# motor_driver.net
KiCad netlist of a schematic drawn in EAGLE
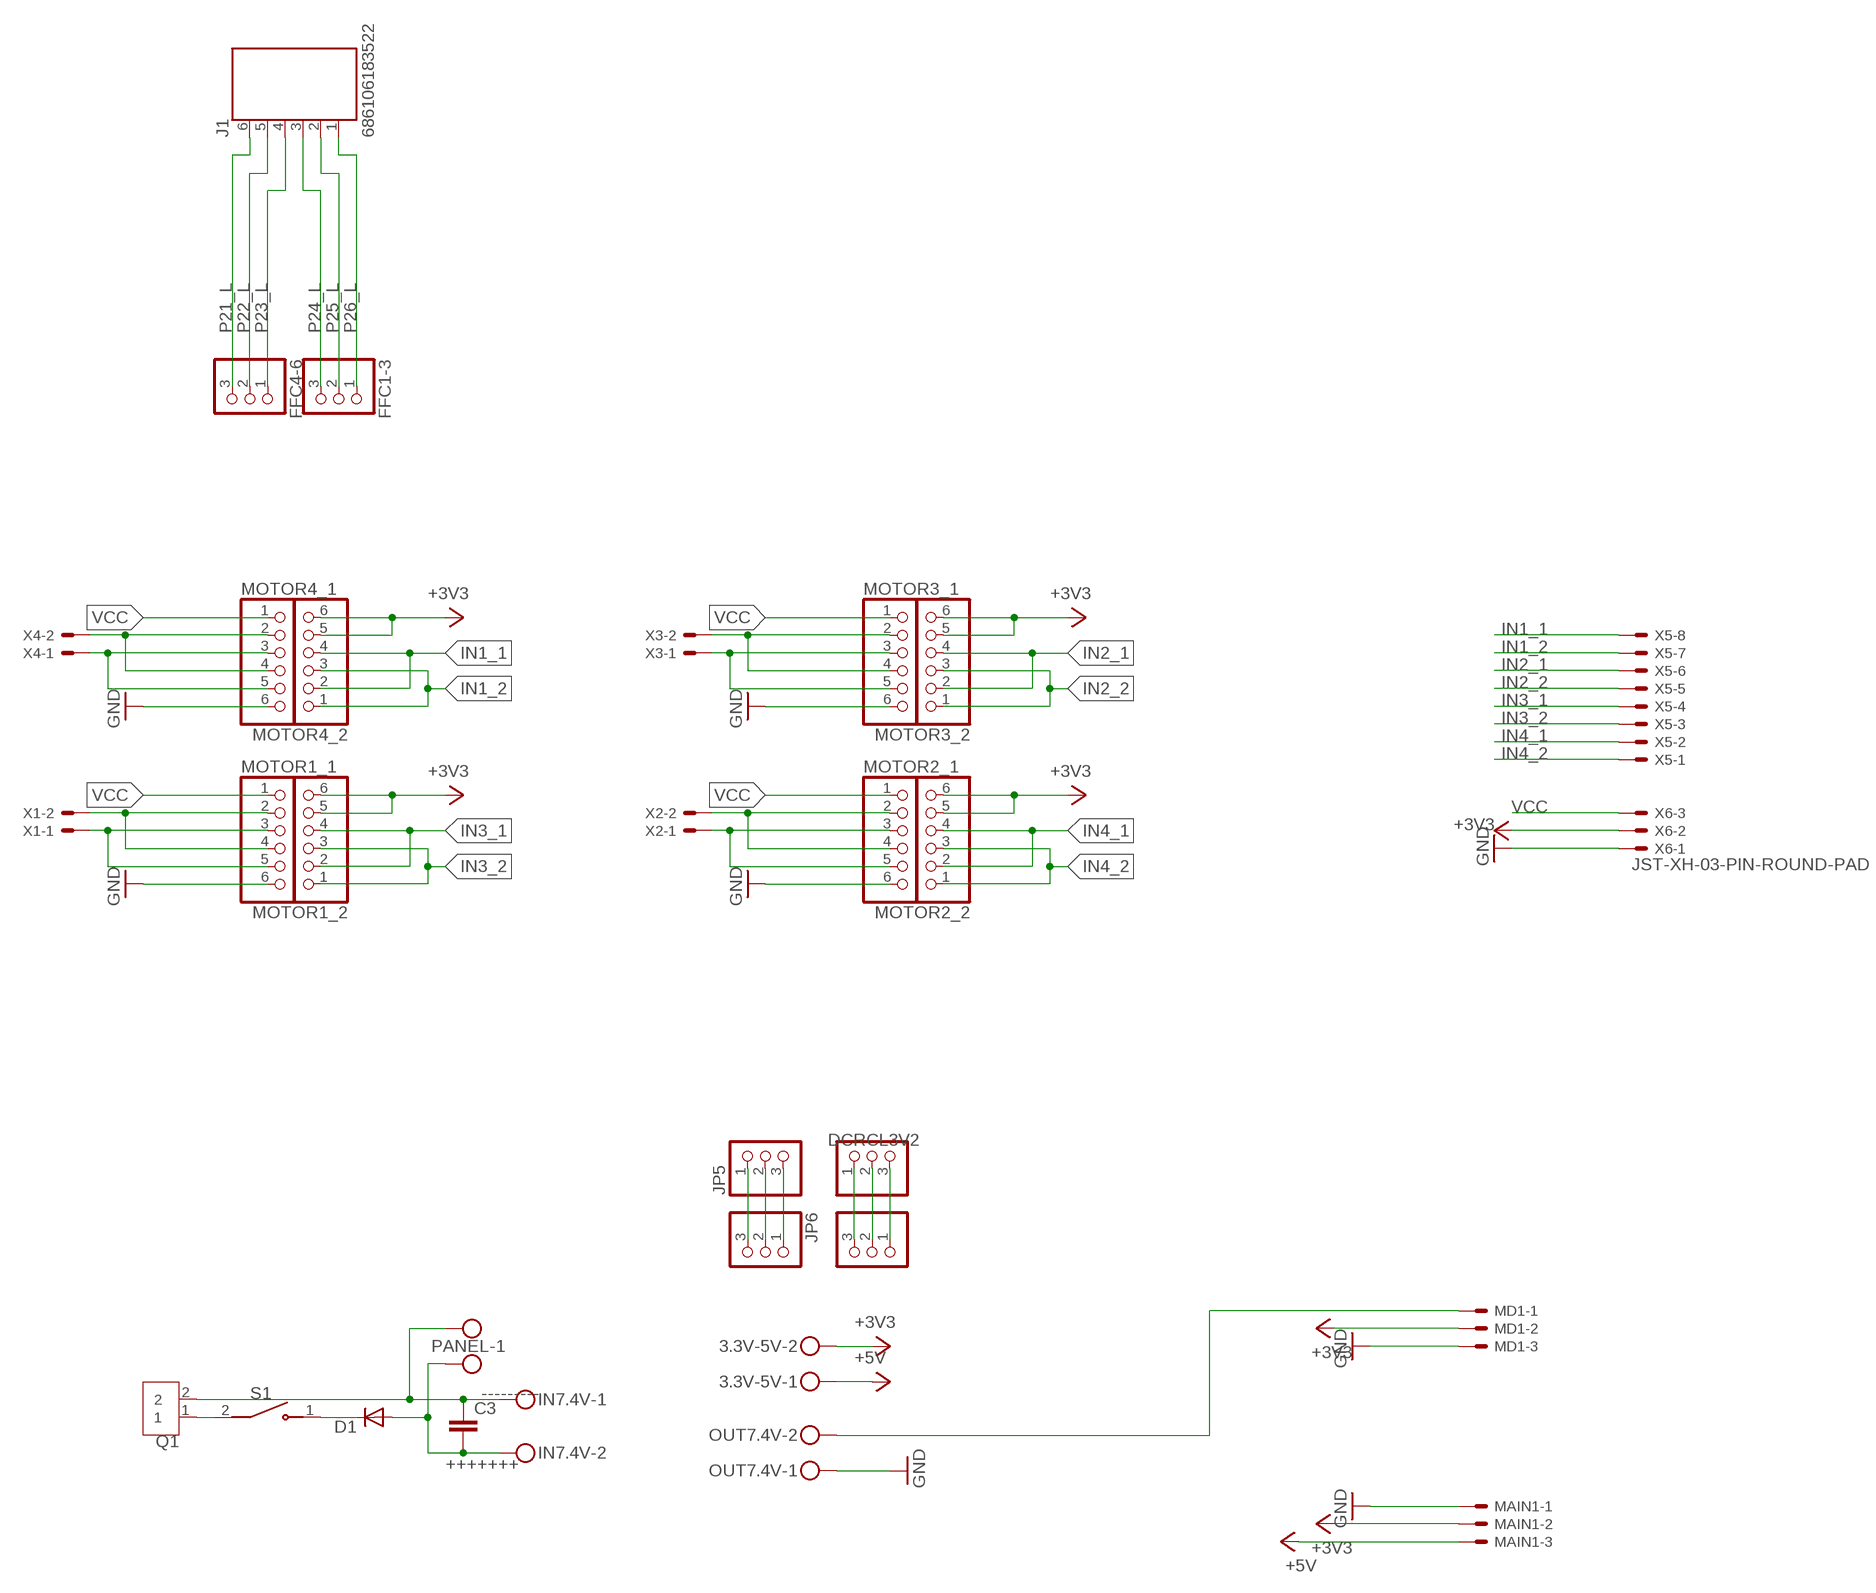
[diagram p0: schematic, sheet 1]

(export (version "E")
  (design (tool "Eeschema 10.0.6"))
  (components
    (comp (ref "3.3V-5V")
      (value "MKDSN1,5/2-5,08")
      (footprint "eagle-import:MKDSN1,5_2-5,08")
      (libsource (lib "eagle-import") (part "MKDSN1,5/2-5,08"))
    )
    (comp (ref "C3")
      (value "C-EU025-030X050")
      (footprint "eagle-import:C025-030X050")
      (libsource (lib "eagle-import") (part "C-EU025-030X050"))
    )
    (comp (ref "D1")
      (value "DIODE-SMC")
      (footprint "eagle-import:SMC")
      (libsource (lib "eagle-import") (part "DIODE-SMC"))
    )
    (comp (ref "DCRC3V1")
      (value "PINHD-1X3")
      (footprint "eagle-import:1X03")
      (libsource (lib "eagle-import") (part "PINHD-1X3"))
    )
    (comp (ref "DCRCL3V2")
      (value "PINHD-1X3")
      (footprint "eagle-import:1X03")
      (libsource (lib "eagle-import") (part "PINHD-1X3"))
    )
    (comp (ref "FFC1-3")
      (value "PINHD-1X03_2.54-S")
      (footprint "eagle-import:1X03-S")
      (libsource (lib "eagle-import") (part "PINHD-1X03_2.54-S"))
    )
    (comp (ref "FFC4-6")
      (value "PINHD-1X03_2.54-S")
      (footprint "eagle-import:1X03-S")
      (libsource (lib "eagle-import") (part "PINHD-1X03_2.54-S"))
    )
    (comp (ref "IN7.4V")
      (value "MKDSN1,5/2-5,08")
      (footprint "eagle-import:MKDSN1,5_2-5,08")
      (libsource (lib "eagle-import") (part "MKDSN1,5/2-5,08"))
    )
    (comp (ref "J1")
      (value "686106183522")
      (footprint "eagle-import:686106183522")
      (fields (field (name "MF") "Wurth Electronics"))
      (libsource (lib "eagle-import") (part "686106183522"))
    )
    (comp (ref "JP5")
      (value "PINHD-1X03_2.54-S")
      (footprint "eagle-import:1X03-S")
      (libsource (lib "eagle-import") (part "PINHD-1X03_2.54-S"))
    )
    (comp (ref "JP6")
      (value "PINHD-1X03_2.54-S")
      (footprint "eagle-import:1X03-S")
      (libsource (lib "eagle-import") (part "PINHD-1X03_2.54-S"))
    )
    (comp (ref "MAIN1")
      (value "JST-XH-03-PIN-ROUND-PAD")
      (footprint "eagle-import:JST-XH-03-PACKAGE-ROUND-PAD")
      (libsource (lib "eagle-import") (part "JST-XH-03-PIN-ROUND-PAD"))
    )
    (comp (ref "MD1")
      (value "JST-XH-03-PIN-ROUND-PAD")
      (footprint "eagle-import:JST-XH-03-PACKAGE-ROUND-PAD")
      (libsource (lib "eagle-import") (part "JST-XH-03-PIN-ROUND-PAD"))
    )
    (comp (ref "MOTOR1_1")
      (value "PINHD-1X06_2.54-S")
      (footprint "eagle-import:1X06-S")
      (libsource (lib "eagle-import") (part "PINHD-1X06_2.54-S"))
    )
    (comp (ref "MOTOR1_2")
      (value "PINHD-1X06_2.54-S")
      (footprint "eagle-import:1X06-S")
      (libsource (lib "eagle-import") (part "PINHD-1X06_2.54-S"))
    )
    (comp (ref "MOTOR2_1")
      (value "PINHD-1X06_2.54-S")
      (footprint "eagle-import:1X06-S")
      (libsource (lib "eagle-import") (part "PINHD-1X06_2.54-S"))
    )
    (comp (ref "MOTOR2_2")
      (value "PINHD-1X06_2.54-S")
      (footprint "eagle-import:1X06-S")
      (libsource (lib "eagle-import") (part "PINHD-1X06_2.54-S"))
    )
    (comp (ref "MOTOR3_1")
      (value "PINHD-1X06_2.54-S")
      (footprint "eagle-import:1X06-S")
      (libsource (lib "eagle-import") (part "PINHD-1X06_2.54-S"))
    )
    (comp (ref "MOTOR3_2")
      (value "PINHD-1X06_2.54-S")
      (footprint "eagle-import:1X06-S")
      (libsource (lib "eagle-import") (part "PINHD-1X06_2.54-S"))
    )
    (comp (ref "MOTOR4_1")
      (value "PINHD-1X06_2.54-S")
      (footprint "eagle-import:1X06-S")
      (libsource (lib "eagle-import") (part "PINHD-1X06_2.54-S"))
    )
    (comp (ref "MOTOR4_2")
      (value "PINHD-1X06_2.54-S")
      (footprint "eagle-import:1X06-S")
      (libsource (lib "eagle-import") (part "PINHD-1X06_2.54-S"))
    )
    (comp (ref "OUT7.4V")
      (value "MKDSN1,5/2-5,08")
      (footprint "eagle-import:MKDSN1,5_2-5,08")
      (libsource (lib "eagle-import") (part "MKDSN1,5/2-5,08"))
    )
    (comp (ref "PANEL")
      (value "MKDSN1,5/2-5,08")
      (footprint "eagle-import:MKDSN1,5_2-5,08")
      (libsource (lib "eagle-import") (part "MKDSN1,5/2-5,08"))
    )
    (comp (ref "Q1")
      (value "XT60_YELLOW")
      (footprint "eagle-import:AMASS_XT60PB-M")
      (fields (field (name "MF") "Pololu") (field (name "MP") "XT60 YELLOW"))
      (libsource (lib "eagle-import") (part "XT60_YELLOW"))
    )
    (comp (ref "S1")
      (value "RR511D1121")
      (footprint "eagle-import:E-SWITCH_RR511D1121")
      (fields (field (name "MF") "E-Switch"))
      (libsource (lib "eagle-import") (part "RR511D1121"))
    )
    (comp (ref "X1")
      (value "JST-XH-02-PIN-ROUND-PAD")
      (footprint "eagle-import:JST-XH-02-PACKAGE-ROUND-PAD")
      (libsource (lib "eagle-import") (part "JST-XH-02-PIN-ROUND-PAD"))
    )
    (comp (ref "X2")
      (value "JST-XH-02-PIN-ROUND-PAD")
      (footprint "eagle-import:JST-XH-02-PACKAGE-ROUND-PAD")
      (libsource (lib "eagle-import") (part "JST-XH-02-PIN-ROUND-PAD"))
    )
    (comp (ref "X3")
      (value "JST-XH-02-PIN-ROUND-PAD")
      (footprint "eagle-import:JST-XH-02-PACKAGE-ROUND-PAD")
      (libsource (lib "eagle-import") (part "JST-XH-02-PIN-ROUND-PAD"))
    )
    (comp (ref "X4")
      (value "JST-XH-02-PIN-ROUND-PAD")
      (footprint "eagle-import:JST-XH-02-PACKAGE-ROUND-PAD")
      (libsource (lib "eagle-import") (part "JST-XH-02-PIN-ROUND-PAD"))
    )
    (comp (ref "X5")
      (value "JST-XH-08-PIN-ROUND-PAD")
      (footprint "eagle-import:JST-XH-08-PACKAGE-ROUND-PAD")
      (libsource (lib "eagle-import") (part "JST-XH-08-PIN-ROUND-PAD"))
    )
    (comp (ref "X6")
      (value "JST-XH-03-PIN-ROUND-PAD")
      (footprint "eagle-import:JST-XH-03-PACKAGE-ROUND-PAD")
      (libsource (lib "eagle-import") (part "JST-XH-03-PIN-ROUND-PAD"))
    )
  )
  (nets
    (net (code "1") (name "+3V3") (class "Default")
      (node (ref "3.3V-5V") (pin "2") (pinfunction "KL_2") (pintype "passive"))
      (node (ref "MAIN1") (pin "2") (pinfunction "S_2") (pintype "passive"))
      (node (ref "MD1") (pin "2") (pinfunction "S_2") (pintype "passive"))
      (node (ref "MOTOR1_2") (pin "5") (pinfunction "5_5") (pintype "passive"))
      (node (ref "MOTOR1_2") (pin "6") (pinfunction "6_6") (pintype "passive"))
      (node (ref "MOTOR2_2") (pin "5") (pinfunction "5_5") (pintype "passive"))
      (node (ref "MOTOR2_2") (pin "6") (pinfunction "6_6") (pintype "passive"))
      (node (ref "MOTOR3_2") (pin "5") (pinfunction "5_5") (pintype "passive"))
      (node (ref "MOTOR3_2") (pin "6") (pinfunction "6_6") (pintype "passive"))
      (node (ref "MOTOR4_2") (pin "5") (pinfunction "5_5") (pintype "passive"))
      (node (ref "MOTOR4_2") (pin "6") (pinfunction "6_6") (pintype "passive"))
      (node (ref "X6") (pin "2") (pinfunction "S_2") (pintype "passive"))
    )
    (net (code "2") (name "+5V") (class "Default")
      (node (ref "3.3V-5V") (pin "1") (pinfunction "KL_1") (pintype "passive"))
      (node (ref "MAIN1") (pin "3") (pinfunction "S_3") (pintype "passive"))
    )
    (net (code "3") (name "/+++++++") (class "Default")
      (node (ref "C3") (pin "2") (pinfunction "2_2") (pintype "passive"))
      (node (ref "D1") (pin "A") (pinfunction "A_A") (pintype "passive"))
      (node (ref "IN7.4V") (pin "2") (pinfunction "KL_2") (pintype "passive"))
      (node (ref "PANEL") (pin "2") (pinfunction "KL_2") (pintype "passive"))
    )
    (net (code "4") (name "/---------") (class "Default")
      (node (ref "C3") (pin "1") (pinfunction "1_1") (pintype "passive"))
      (node (ref "IN7.4V") (pin "1") (pinfunction "KL_1") (pintype "passive"))
      (node (ref "PANEL") (pin "1") (pinfunction "KL_1") (pintype "passive"))
      (node (ref "Q1") (pin "2") (pinfunction "2_2") (pintype "passive"))
    )
    (net (code "5") (name "/P21_L") (class "Default")
      (node (ref "FFC4-6") (pin "3") (pinfunction "3_3") (pintype "passive"))
      (node (ref "J1") (pin "6") (pinfunction "1_6") (pintype "passive"))
    )
    (net (code "6") (name "/P22_L") (class "Default")
      (node (ref "FFC4-6") (pin "2") (pinfunction "2_2") (pintype "passive"))
      (node (ref "J1") (pin "5") (pinfunction "2_5") (pintype "passive"))
    )
    (net (code "7") (name "/P23_L") (class "Default")
      (node (ref "FFC4-6") (pin "1") (pinfunction "1_1") (pintype "passive"))
      (node (ref "J1") (pin "4") (pinfunction "3_4") (pintype "passive"))
    )
    (net (code "8") (name "/P24_L") (class "Default")
      (node (ref "FFC1-3") (pin "3") (pinfunction "3_3") (pintype "passive"))
      (node (ref "J1") (pin "3") (pinfunction "4_3") (pintype "passive"))
    )
    (net (code "9") (name "/P25_L") (class "Default")
      (node (ref "FFC1-3") (pin "2") (pinfunction "2_2") (pintype "passive"))
      (node (ref "J1") (pin "2") (pinfunction "5_2") (pintype "passive"))
    )
    (net (code "10") (name "/P26_L") (class "Default")
      (node (ref "FFC1-3") (pin "1") (pinfunction "1_1") (pintype "passive"))
      (node (ref "J1") (pin "1") (pinfunction "6_1") (pintype "passive"))
    )
    (net (code "11") (name "GND") (class "Default")
      (node (ref "MAIN1") (pin "1") (pinfunction "S_1") (pintype "passive"))
      (node (ref "MD1") (pin "3") (pinfunction "S_3") (pintype "passive"))
      (node (ref "MOTOR1_1") (pin "6") (pinfunction "6_6") (pintype "passive"))
      (node (ref "MOTOR2_1") (pin "6") (pinfunction "6_6") (pintype "passive"))
      (node (ref "MOTOR3_1") (pin "6") (pinfunction "6_6") (pintype "passive"))
      (node (ref "MOTOR4_1") (pin "6") (pinfunction "6_6") (pintype "passive"))
      (node (ref "OUT7.4V") (pin "1") (pinfunction "KL_1") (pintype "passive"))
      (node (ref "X6") (pin "1") (pinfunction "S_1") (pintype "passive"))
    )
    (net (code "12") (name "IN1_1") (class "Default")
      (node (ref "MOTOR4_2") (pin "2") (pinfunction "2_2") (pintype "passive"))
      (node (ref "MOTOR4_2") (pin "4") (pinfunction "4_4") (pintype "passive"))
      (node (ref "X5") (pin "8") (pinfunction "S_8") (pintype "passive"))
    )
    (net (code "13") (name "IN1_2") (class "Default")
      (node (ref "MOTOR4_2") (pin "1") (pinfunction "1_1") (pintype "passive"))
      (node (ref "MOTOR4_2") (pin "3") (pinfunction "3_3") (pintype "passive"))
      (node (ref "X5") (pin "7") (pinfunction "S_7") (pintype "passive"))
    )
    (net (code "14") (name "IN2_1") (class "Default")
      (node (ref "MOTOR3_2") (pin "2") (pinfunction "2_2") (pintype "passive"))
      (node (ref "MOTOR3_2") (pin "4") (pinfunction "4_4") (pintype "passive"))
      (node (ref "X5") (pin "6") (pinfunction "S_6") (pintype "passive"))
    )
    (net (code "15") (name "IN2_2") (class "Default")
      (node (ref "MOTOR3_2") (pin "1") (pinfunction "1_1") (pintype "passive"))
      (node (ref "MOTOR3_2") (pin "3") (pinfunction "3_3") (pintype "passive"))
      (node (ref "X5") (pin "5") (pinfunction "S_5") (pintype "passive"))
    )
    (net (code "16") (name "IN3_1") (class "Default")
      (node (ref "MOTOR1_2") (pin "2") (pinfunction "2_2") (pintype "passive"))
      (node (ref "MOTOR1_2") (pin "4") (pinfunction "4_4") (pintype "passive"))
      (node (ref "X5") (pin "4") (pinfunction "S_4") (pintype "passive"))
    )
    (net (code "17") (name "IN3_2") (class "Default")
      (node (ref "MOTOR1_2") (pin "1") (pinfunction "1_1") (pintype "passive"))
      (node (ref "MOTOR1_2") (pin "3") (pinfunction "3_3") (pintype "passive"))
      (node (ref "X5") (pin "3") (pinfunction "S_3") (pintype "passive"))
    )
    (net (code "18") (name "IN4_1") (class "Default")
      (node (ref "MOTOR2_2") (pin "2") (pinfunction "2_2") (pintype "passive"))
      (node (ref "MOTOR2_2") (pin "4") (pinfunction "4_4") (pintype "passive"))
      (node (ref "X5") (pin "2") (pinfunction "S_2") (pintype "passive"))
    )
    (net (code "19") (name "IN4_2") (class "Default")
      (node (ref "MOTOR2_2") (pin "1") (pinfunction "1_1") (pintype "passive"))
      (node (ref "MOTOR2_2") (pin "3") (pinfunction "3_3") (pintype "passive"))
      (node (ref "X5") (pin "1") (pinfunction "S_1") (pintype "passive"))
    )
    (net (code "20") (name "Net-(DCRC3V1-Pad1)") (class "Default")
      (node (ref "DCRC3V1") (pin "1") (pinfunction "1_1") (pintype "passive"))
      (node (ref "DCRCL3V2") (pin "3") (pinfunction "3_3") (pintype "passive"))
    )
    (net (code "21") (name "Net-(DCRC3V1-Pad2)") (class "Default")
      (node (ref "DCRC3V1") (pin "2") (pinfunction "2_2") (pintype "passive"))
      (node (ref "DCRCL3V2") (pin "2") (pinfunction "2_2") (pintype "passive"))
    )
    (net (code "22") (name "Net-(DCRC3V1-Pad3)") (class "Default")
      (node (ref "DCRC3V1") (pin "3") (pinfunction "3_3") (pintype "passive"))
      (node (ref "DCRCL3V2") (pin "1") (pinfunction "1_1") (pintype "passive"))
    )
    (net (code "23") (name "Net-(JP5-Pad1)") (class "Default")
      (node (ref "JP5") (pin "1") (pinfunction "1_1") (pintype "passive"))
      (node (ref "JP6") (pin "3") (pinfunction "3_3") (pintype "passive"))
    )
    (net (code "24") (name "Net-(JP5-Pad2)") (class "Default")
      (node (ref "JP5") (pin "2") (pinfunction "2_2") (pintype "passive"))
      (node (ref "JP6") (pin "2") (pinfunction "2_2") (pintype "passive"))
    )
    (net (code "25") (name "Net-(JP5-Pad3)") (class "Default")
      (node (ref "JP5") (pin "3") (pinfunction "3_3") (pintype "passive"))
      (node (ref "JP6") (pin "1") (pinfunction "1_1") (pintype "passive"))
    )
    (net (code "26") (name "Net-(MD1A-S)") (class "Default")
      (node (ref "MD1") (pin "1") (pinfunction "S_1") (pintype "passive"))
      (node (ref "OUT7.4V") (pin "2") (pinfunction "KL_2") (pintype "passive"))
    )
    (net (code "27") (name "Net-(S1-COM)") (class "Default")
      (node (ref "Q1") (pin "1") (pinfunction "1_1") (pintype "passive"))
      (node (ref "S1") (pin "2") (pinfunction "COM_2") (pintype "passive"))
    )
    (net (code "28") (name "Net-(S1-NO)") (class "Default")
      (node (ref "D1") (pin "C") (pinfunction "C_C") (pintype "passive"))
      (node (ref "S1") (pin "1") (pinfunction "NO_1") (pintype "passive"))
    )
    (net (code "29") (name "Net-(X1A-S)") (class "Default")
      (node (ref "MOTOR1_1") (pin "3") (pinfunction "3_3") (pintype "passive"))
      (node (ref "MOTOR1_1") (pin "5") (pinfunction "5_5") (pintype "passive"))
      (node (ref "X1") (pin "1") (pinfunction "S_1") (pintype "passive"))
    )
    (net (code "30") (name "Net-(X1B-S)") (class "Default")
      (node (ref "MOTOR1_1") (pin "2") (pinfunction "2_2") (pintype "passive"))
      (node (ref "MOTOR1_1") (pin "4") (pinfunction "4_4") (pintype "passive"))
      (node (ref "X1") (pin "2") (pinfunction "S_2") (pintype "passive"))
    )
    (net (code "31") (name "Net-(X2A-S)") (class "Default")
      (node (ref "MOTOR2_1") (pin "3") (pinfunction "3_3") (pintype "passive"))
      (node (ref "MOTOR2_1") (pin "5") (pinfunction "5_5") (pintype "passive"))
      (node (ref "X2") (pin "1") (pinfunction "S_1") (pintype "passive"))
    )
    (net (code "32") (name "Net-(X2B-S)") (class "Default")
      (node (ref "MOTOR2_1") (pin "2") (pinfunction "2_2") (pintype "passive"))
      (node (ref "MOTOR2_1") (pin "4") (pinfunction "4_4") (pintype "passive"))
      (node (ref "X2") (pin "2") (pinfunction "S_2") (pintype "passive"))
    )
    (net (code "33") (name "Net-(X3A-S)") (class "Default")
      (node (ref "MOTOR3_1") (pin "3") (pinfunction "3_3") (pintype "passive"))
      (node (ref "MOTOR3_1") (pin "5") (pinfunction "5_5") (pintype "passive"))
      (node (ref "X3") (pin "1") (pinfunction "S_1") (pintype "passive"))
    )
    (net (code "34") (name "Net-(X3B-S)") (class "Default")
      (node (ref "MOTOR3_1") (pin "2") (pinfunction "2_2") (pintype "passive"))
      (node (ref "MOTOR3_1") (pin "4") (pinfunction "4_4") (pintype "passive"))
      (node (ref "X3") (pin "2") (pinfunction "S_2") (pintype "passive"))
    )
    (net (code "35") (name "Net-(X4A-S)") (class "Default")
      (node (ref "MOTOR4_1") (pin "3") (pinfunction "3_3") (pintype "passive"))
      (node (ref "MOTOR4_1") (pin "5") (pinfunction "5_5") (pintype "passive"))
      (node (ref "X4") (pin "1") (pinfunction "S_1") (pintype "passive"))
    )
    (net (code "36") (name "Net-(X4B-S)") (class "Default")
      (node (ref "MOTOR4_1") (pin "2") (pinfunction "2_2") (pintype "passive"))
      (node (ref "MOTOR4_1") (pin "4") (pinfunction "4_4") (pintype "passive"))
      (node (ref "X4") (pin "2") (pinfunction "S_2") (pintype "passive"))
    )
    (net (code "37") (name "VCC") (class "Default")
      (node (ref "MOTOR1_1") (pin "1") (pinfunction "1_1") (pintype "passive"))
      (node (ref "MOTOR2_1") (pin "1") (pinfunction "1_1") (pintype "passive"))
      (node (ref "MOTOR3_1") (pin "1") (pinfunction "1_1") (pintype "passive"))
      (node (ref "MOTOR4_1") (pin "1") (pinfunction "1_1") (pintype "passive"))
      (node (ref "X6") (pin "3") (pinfunction "S_3") (pintype "passive"))
    )
  )
)
